# PowerInput.net
KiCad netlist of a schematic drawn in Altium Designer
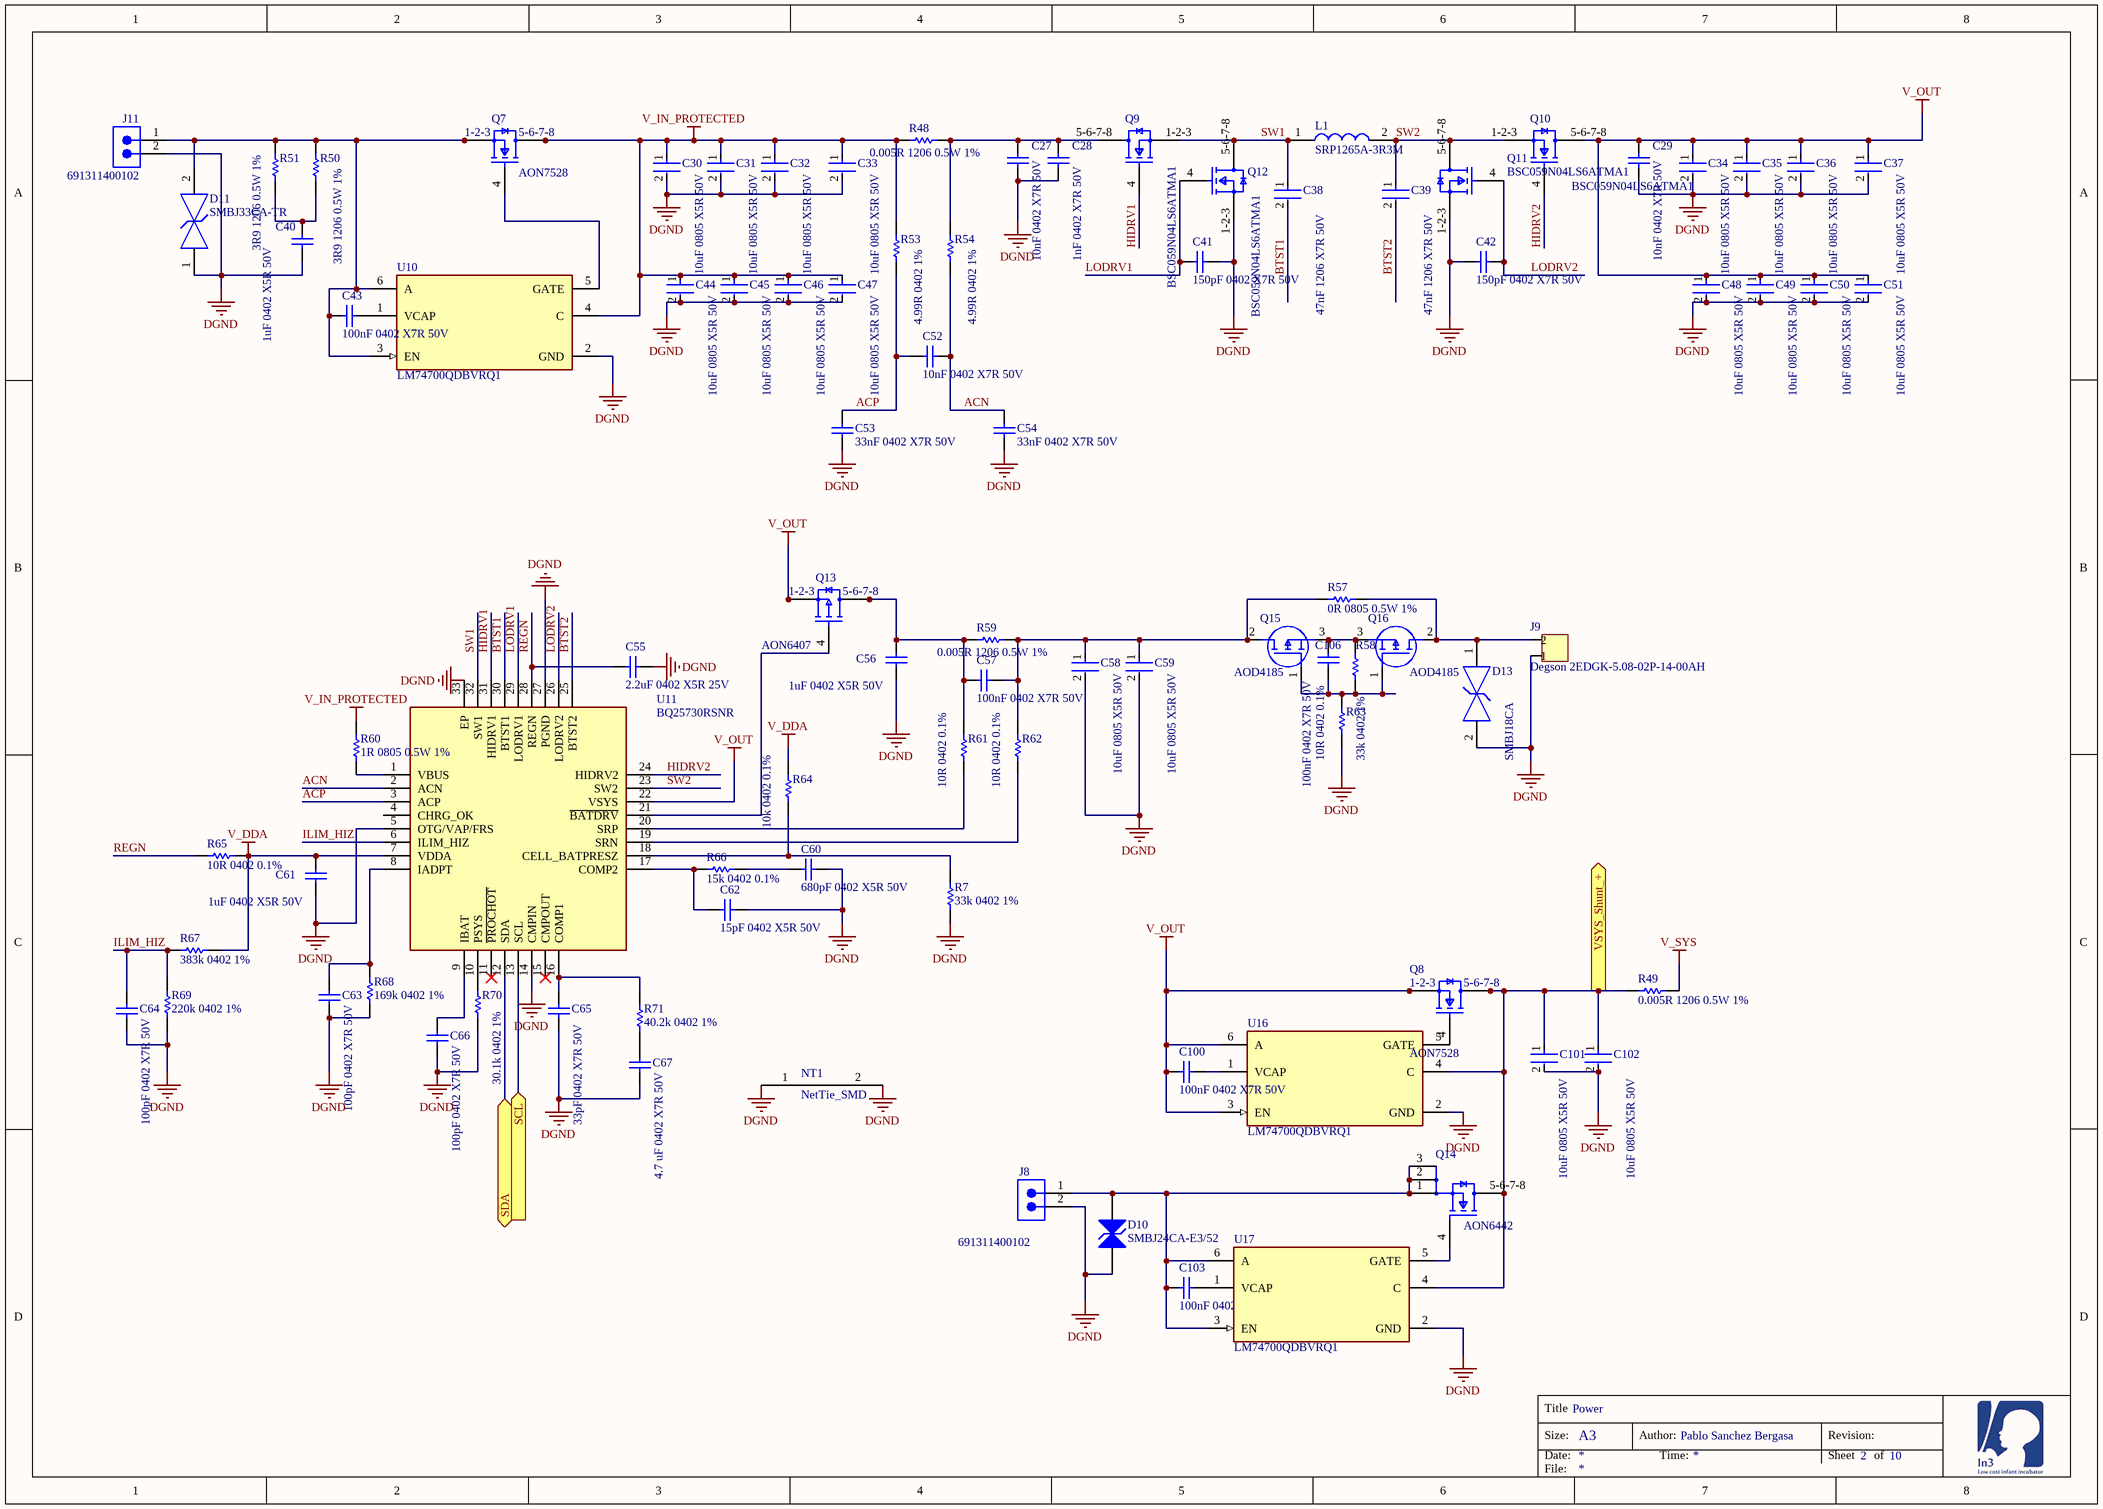
[diagram p0: PowerInput.SchDoc]

(export (version "E")
  (design (tool "Eeschema 10.0.6"))
  (components
    (comp (ref "C27")
      (value "10nF 0402 X7R 50V")
      (footprint "CAPC1005X55X25NL5T10")
      (libsource (lib "Altium Content Vault") (part "CAP-NP-2"))
    )
    (comp (ref "C28")
      (value "1nF 0402 X7R 50V")
      (footprint "CAPC1005X55X25NL5T10")
      (libsource (lib "Altium Content Vault") (part "CAP-NP-2"))
    )
    (comp (ref "C29")
      (value "10nF 0402 X7R 50V")
      (footprint "CAPC1005X55X25NL5T10")
      (libsource (lib "Altium Content Vault") (part "CAP-NP-2"))
    )
    (comp (ref "C30")
      (value "10uF 0805 X5R 50V")
      (footprint "FP-GRM21B-0_2-e0_2_0_7-MFG")
      (description "Chip Multilayer Ceramic Capacitors for General Purpose, 0805, 10uF, X5R, 15%, 10%, 35V")
      (fields (field (name "TOLERANCE") "10%"))
      (libsource (lib "Altium Content Vault") (part "b4654b650e69147ec39a6b967a45e02"))
    )
    (comp (ref "C31")
      (value "10uF 0805 X5R 50V")
      (footprint "FP-GRM21B-0_2-e0_2_0_7-MFG")
      (description "Chip Multilayer Ceramic Capacitors for General Purpose, 0805, 10uF, X5R, 15%, 10%, 35V")
      (fields (field (name "TOLERANCE") "10%"))
      (libsource (lib "Altium Content Vault") (part "b4654b650e69147ec39a6b967a45e02"))
    )
    (comp (ref "C32")
      (value "10uF 0805 X5R 50V")
      (footprint "FP-GRM21B-0_2-e0_2_0_7-MFG")
      (description "Chip Multilayer Ceramic Capacitors for General Purpose, 0805, 10uF, X5R, 15%, 10%, 35V")
      (fields (field (name "TOLERANCE") "10%"))
      (libsource (lib "Altium Content Vault") (part "b4654b650e69147ec39a6b967a45e02"))
    )
    (comp (ref "C33")
      (value "10uF 0805 X5R 50V")
      (footprint "FP-GRM21B-0_2-e0_2_0_7-MFG")
      (description "Chip Multilayer Ceramic Capacitors for General Purpose, 0805, 10uF, X5R, 15%, 10%, 35V")
      (fields (field (name "TOLERANCE") "10%"))
      (libsource (lib "Altium Content Vault") (part "b4654b650e69147ec39a6b967a45e02"))
    )
    (comp (ref "C34")
      (value "10uF 0805 X5R 50V")
      (footprint "FP-GRM21B-0_2-e0_2_0_7-MFG")
      (description "Chip Multilayer Ceramic Capacitors for General Purpose, 0805, 10uF, X5R, 15%, 10%, 35V")
      (fields (field (name "TOLERANCE") "10%"))
      (libsource (lib "Altium Content Vault") (part "b4654b650e69147ec39a6b967a45e02"))
    )
    (comp (ref "C35")
      (value "10uF 0805 X5R 50V")
      (footprint "FP-GRM21B-0_2-e0_2_0_7-MFG")
      (description "Chip Multilayer Ceramic Capacitors for General Purpose, 0805, 10uF, X5R, 15%, 10%, 35V")
      (fields (field (name "TOLERANCE") "10%"))
      (libsource (lib "Altium Content Vault") (part "b4654b650e69147ec39a6b967a45e02"))
    )
    (comp (ref "C36")
      (value "10uF 0805 X5R 50V")
      (footprint "FP-GRM21B-0_2-e0_2_0_7-MFG")
      (description "Chip Multilayer Ceramic Capacitors for General Purpose, 0805, 10uF, X5R, 15%, 10%, 35V")
      (fields (field (name "TOLERANCE") "10%"))
      (libsource (lib "Altium Content Vault") (part "b4654b650e69147ec39a6b967a45e02"))
    )
    (comp (ref "C37")
      (value "10uF 0805 X5R 50V")
      (footprint "FP-GRM21B-0_2-e0_2_0_7-MFG")
      (description "Chip Multilayer Ceramic Capacitors for General Purpose, 0805, 10uF, X5R, 15%, 10%, 35V")
      (fields (field (name "TOLERANCE") "10%"))
      (libsource (lib "Altium Content Vault") (part "b4654b650e69147ec39a6b967a45e02"))
    )
    (comp (ref "C38")
      (value "47nF 1206 X7R 50V")
      (footprint "FP-CC1206-FD-MFG")
      (description "CAP CER 10UF 50V X5R 1206")
      (fields (field (name "TOLERANCE") "10%"))
      (libsource (lib "Altium Content Vault") (part "b4654b650e69147ec39a6b967a45e02"))
    )
    (comp (ref "C39")
      (value "47nF 1206 X7R 50V")
      (footprint "FP-CC1206-FD-MFG")
      (description "CAP CER 10UF 50V X5R 1206")
      (fields (field (name "TOLERANCE") "10%"))
      (libsource (lib "Altium Content Vault") (part "b4654b650e69147ec39a6b967a45e02"))
    )
    (comp (ref "C40")
      (value "1uF 0402 X5R 50V")
      (footprint "CAPC1005X55X25NL5T10")
      (libsource (lib "Altium Content Vault") (part "CAP-NP-2"))
    )
    (comp (ref "C41")
      (value "150pF 0402 X7R 50V")
      (footprint "CAPC1005X55X25NL5T10")
      (libsource (lib "Altium Content Vault") (part "CAP-NP-2"))
    )
    (comp (ref "C42")
      (value "150pF 0402 X7R 50V")
      (footprint "CAPC1005X55X25NL5T10")
      (libsource (lib "Altium Content Vault") (part "CAP-NP-2"))
    )
    (comp (ref "C43")
      (value "100nF 0402 X7R 50V")
      (footprint "CAPC1005X55X25NL5T10")
      (libsource (lib "Altium Content Vault") (part "CAP-NP-2"))
    )
    (comp (ref "C44")
      (value "10uF 0805 X5R 50V")
      (footprint "FP-GRM21B-0_2-e0_2_0_7-MFG")
      (description "Chip Multilayer Ceramic Capacitors for General Purpose, 0805, 10uF, X5R, 15%, 10%, 35V")
      (fields (field (name "TOLERANCE") "10%"))
      (libsource (lib "Altium Content Vault") (part "b4654b650e69147ec39a6b967a45e02"))
    )
    (comp (ref "C45")
      (value "10uF 0805 X5R 50V")
      (footprint "FP-GRM21B-0_2-e0_2_0_7-MFG")
      (description "Chip Multilayer Ceramic Capacitors for General Purpose, 0805, 10uF, X5R, 15%, 10%, 35V")
      (fields (field (name "TOLERANCE") "10%"))
      (libsource (lib "Altium Content Vault") (part "b4654b650e69147ec39a6b967a45e02"))
    )
    (comp (ref "C46")
      (value "10uF 0805 X5R 50V")
      (footprint "FP-GRM21B-0_2-e0_2_0_7-MFG")
      (description "Chip Multilayer Ceramic Capacitors for General Purpose, 0805, 10uF, X5R, 15%, 10%, 35V")
      (fields (field (name "TOLERANCE") "10%"))
      (libsource (lib "Altium Content Vault") (part "b4654b650e69147ec39a6b967a45e02"))
    )
    (comp (ref "C47")
      (value "10uF 0805 X5R 50V")
      (footprint "FP-GRM21B-0_2-e0_2_0_7-MFG")
      (description "Chip Multilayer Ceramic Capacitors for General Purpose, 0805, 10uF, X5R, 15%, 10%, 35V")
      (fields (field (name "TOLERANCE") "10%"))
      (libsource (lib "Altium Content Vault") (part "b4654b650e69147ec39a6b967a45e02"))
    )
    (comp (ref "C48")
      (value "10uF 0805 X5R 50V")
      (footprint "FP-GRM21B-0_2-e0_2_0_7-MFG")
      (description "Chip Multilayer Ceramic Capacitors for General Purpose, 0805, 10uF, X5R, 15%, 10%, 35V")
      (fields (field (name "TOLERANCE") "10%"))
      (libsource (lib "Altium Content Vault") (part "b4654b650e69147ec39a6b967a45e02"))
    )
    (comp (ref "C49")
      (value "10uF 0805 X5R 50V")
      (footprint "FP-GRM21B-0_2-e0_2_0_7-MFG")
      (description "Chip Multilayer Ceramic Capacitors for General Purpose, 0805, 10uF, X5R, 15%, 10%, 35V")
      (fields (field (name "TOLERANCE") "10%"))
      (libsource (lib "Altium Content Vault") (part "b4654b650e69147ec39a6b967a45e02"))
    )
    (comp (ref "C50")
      (value "10uF 0805 X5R 50V")
      (footprint "FP-GRM21B-0_2-e0_2_0_7-MFG")
      (description "Chip Multilayer Ceramic Capacitors for General Purpose, 0805, 10uF, X5R, 15%, 10%, 35V")
      (fields (field (name "TOLERANCE") "10%"))
      (libsource (lib "Altium Content Vault") (part "b4654b650e69147ec39a6b967a45e02"))
    )
    (comp (ref "C51")
      (value "10uF 0805 X5R 50V")
      (footprint "FP-GRM21B-0_2-e0_2_0_7-MFG")
      (description "Chip Multilayer Ceramic Capacitors for General Purpose, 0805, 10uF, X5R, 15%, 10%, 35V")
      (fields (field (name "TOLERANCE") "10%"))
      (libsource (lib "Altium Content Vault") (part "b4654b650e69147ec39a6b967a45e02"))
    )
    (comp (ref "C52")
      (value "10nF 0402 X7R 50V")
      (footprint "CAPC1005X55X25NL5T10")
      (libsource (lib "Altium Content Vault") (part "CAP-NP-2"))
    )
    (comp (ref "C53")
      (value "33nF 0402 X7R 50V")
      (footprint "CAPC1005X55X25NL5T10")
      (libsource (lib "Altium Content Vault") (part "CAP-NP-2"))
    )
    (comp (ref "C54")
      (value "33nF 0402 X7R 50V")
      (footprint "CAPC1005X55X25NL5T10")
      (libsource (lib "Altium Content Vault") (part "CAP-NP-2"))
    )
    (comp (ref "C55")
      (value "2.2uF 0402 X5R 25V")
      (footprint "CAPC1005X55X25NL5T10")
      (libsource (lib "Altium Content Vault") (part "CAP-NP-2"))
    )
    (comp (ref "C56")
      (value "1uF 0402 X5R 50V")
      (footprint "CAPC1005X55X25NL5T10")
      (libsource (lib "Altium Content Vault") (part "CAP-NP-2"))
    )
    (comp (ref "C57")
      (value "100nF 0402 X7R 50V")
      (footprint "CAPC1005X55X25NL5T10")
      (libsource (lib "Altium Content Vault") (part "CAP-NP-2"))
    )
    (comp (ref "C58")
      (value "10uF 0805 X5R 50V")
      (footprint "FP-GRM21B-0_2-e0_2_0_7-MFG")
      (description "Chip Multilayer Ceramic Capacitors for General Purpose, 0805, 10uF, X5R, 15%, 10%, 35V")
      (fields (field (name "TOLERANCE") "10%"))
      (libsource (lib "Altium Content Vault") (part "b4654b650e69147ec39a6b967a45e02"))
    )
    (comp (ref "C59")
      (value "10uF 0805 X5R 50V")
      (footprint "FP-GRM21B-0_2-e0_2_0_7-MFG")
      (description "Chip Multilayer Ceramic Capacitors for General Purpose, 0805, 10uF, X5R, 15%, 10%, 35V")
      (fields (field (name "TOLERANCE") "10%"))
      (libsource (lib "Altium Content Vault") (part "b4654b650e69147ec39a6b967a45e02"))
    )
    (comp (ref "C60")
      (value "680pF 0402 X5R 50V")
      (footprint "CAPC1005X55X25NL5T10")
      (libsource (lib "Altium Content Vault") (part "CAP-NP-2"))
    )
    (comp (ref "C61")
      (value "1uF 0402 X5R 50V")
      (footprint "CAPC1005X55X25NL5T10")
      (libsource (lib "Altium Content Vault") (part "CAP-NP-2"))
    )
    (comp (ref "C62")
      (value "15pF 0402 X5R 50V")
      (footprint "CAPC1005X55X25NL5T10")
      (libsource (lib "Altium Content Vault") (part "CAP-NP-2"))
    )
    (comp (ref "C63")
      (value "100pF 0402 X7R 50V")
      (footprint "CAPC1005X55X25NL5T10")
      (libsource (lib "Altium Content Vault") (part "CAP-NP-2"))
    )
    (comp (ref "C64")
      (value "100pF 0402 X7R 50V")
      (footprint "CAPC1005X55X25NL5T10")
      (libsource (lib "Altium Content Vault") (part "CAP-NP-2"))
    )
    (comp (ref "C65")
      (value "33pF 0402 X7R 50V")
      (footprint "CAPC1005X55X25NL5T10")
      (libsource (lib "Altium Content Vault") (part "CAP-NP-2"))
    )
    (comp (ref "C66")
      (value "100pF 0402 X7R 50V")
      (footprint "CAPC1005X55X25NL5T10")
      (libsource (lib "Altium Content Vault") (part "CAP-NP-2"))
    )
    (comp (ref "C67")
      (value "4.7 uF 0402 X7R 50V")
      (footprint "CAPC1005X55X25NL5T10")
      (libsource (lib "Altium Content Vault") (part "CAP-NP-2"))
    )
    (comp (ref "C100")
      (value "100nF 0402 X7R 50V")
      (footprint "CAPC1005X55X25NL5T10")
      (libsource (lib "Altium Content Vault") (part "CAP-NP-2"))
    )
    (comp (ref "C101")
      (value "10uF 0805 X5R 50V")
      (footprint "FP-GRM21B-0_2-e0_2_0_7-MFG")
      (description "Chip Multilayer Ceramic Capacitors for General Purpose, 0805, 10uF, X5R, 15%, 10%, 35V")
      (fields (field (name "TOLERANCE") "10%"))
      (libsource (lib "Altium Content Vault") (part "b4654b650e69147ec39a6b967a45e02"))
    )
    (comp (ref "C102")
      (value "10uF 0805 X5R 50V")
      (footprint "FP-GRM21B-0_2-e0_2_0_7-MFG")
      (description "Chip Multilayer Ceramic Capacitors for General Purpose, 0805, 10uF, X5R, 15%, 10%, 35V")
      (fields (field (name "TOLERANCE") "10%"))
      (libsource (lib "Altium Content Vault") (part "b4654b650e69147ec39a6b967a45e02"))
    )
    (comp (ref "C103")
      (value "100nF 0402 X7R 50V")
      (footprint "CAPC1005X55X25NL5T10")
      (libsource (lib "Altium Content Vault") (part "CAP-NP-2"))
    )
    (comp (ref "C106")
      (value "100nF 0402 X7R 50V")
      (footprint "CAPC1005X55X25NL5T10")
      (libsource (lib "Altium Content Vault") (part "CAP-NP-2"))
    )
    (comp (ref "D10")
      (value "SMBJ24CA-E3/52")
      (footprint "VISH-DO-214AA-A-2_V")
      (fields (field (name "MANUFACTURER") "Vishay"))
      (libsource (lib "Altium Content Vault") (part "DZEN-AA-2"))
    )
    (comp (ref "D11")
      (value "SMBJ33CA-TR")
      (footprint "FP-SMB-CA-MFG")
      (description "TVS DIODE 33V 69.7V SMB")
      (fields
        (field (name "OCTOPART") "https://octopart.com/smbj33ca-tr-stmicroelectronics-347069")
        (field (name "MANUFACTURER") "STMicroelectronics")
      )
      (libsource (lib "Altium Content Vault") (part "11bd9d59d340f0612179daf16ad9b72"))
    )
    (comp (ref "D13")
      (value "SMBJ18CA")
      (footprint "FP-SMBJ-MFG")
      (description "TVS DIODE 18V 29.2V DO214AA")
      (fields
        (field (name "MANUFACTURER") "Littelfuse Inc")
        (field (name "OCTOPART") "https://octopart.com/smbj18ca-littelfuse-350695")
      )
      (libsource (lib "Altium Content Vault") (part "876f4347bf90aa6f500f43e3cd03972"))
    )
    (comp (ref "J8")
      (value "691311400102")
      (footprint "691311400102")
      (description "7.62MM Pitch Straight Pluggable Term Block, Pcb Header, Through Hole, 2 Way")
      (fields (field (name "VOLTAGE") "300V"))
      (libsource (lib "Altium Content Vault") (part "TBL - 1R - 02P - Male"))
    )
    (comp (ref "J9")
      (value "Degson 2EDGK-5.08-02P-14-00AH")
      (footprint "PCB-h4cyb3wxd4gf7j132tzl-1")
      (description "Terminal block, 5mm 2 Pos, through hole male.")
      (fields (field (name "MANUFACTURER PART NUMBER") "2EDGK-5.08-02P-14-00AH + 2EDGVC-5.08-02P"))
      (libsource (lib "in3ator") (part "CMP-7a42b7ee166ba585-1"))
    )
    (comp (ref "J11")
      (value "691311400102")
      (footprint "691311400102")
      (description "7.62MM Pitch Straight Pluggable Term Block, Pcb Header, Through Hole, 2 Way")
      (fields (field (name "VOLTAGE") "300V"))
      (libsource (lib "Altium Content Vault") (part "TBL - 1R - 02P - Male"))
    )
    (comp (ref "L1")
      (value "SRP1265A-3R3M")
      (footprint "SamacSys:INDPM135125X650N")
      (description "Inductor")
      (fields (field (name "MOUSER PART NUMBER") "652-SRP1265A-3R3M"))
      (libsource (lib "*") (part "SRP1265A-3R3M"))
    )
    (comp (ref "NT1")
      (value "NetTie_SMD")
      (footprint "NETTIE_SMD")
      (description "Net Tie SMD")
      (libsource (lib "net_tie") (part "NetTie_SMD"))
    )
    (comp (ref "Q7")
      (value "AON7528")
      (footprint "SamacSys:AON7520")
      (description "MOSFET (N-Channel)")
      (libsource (lib "SamacSys") (part "AON7528"))
    )
    (comp (ref "Q8")
      (value "AON7528")
      (footprint "SamacSys:AON7520")
      (description "MOSFET (N-Channel)")
      (libsource (lib "SamacSys") (part "AON7528"))
    )
    (comp (ref "Q9")
      (value "BSC059N04LS6ATMA1")
      (footprint "FP-PG-TDSON-8-MFG")
      (description "TRENCH <= 40V")
      (fields
        (field (name "MANUFACTURER") "Infineon")
        (field (name "OCTOPART") "https://octopart.com/bsc059n04ls6atma1-infineon-98039929")
      )
      (libsource (lib "Altium Content Vault") (part "1b0cff3a23bd3632373e77d40b07099"))
    )
    (comp (ref "Q10")
      (value "BSC059N04LS6ATMA1")
      (footprint "FP-PG-TDSON-8-MFG")
      (description "TRENCH <= 40V")
      (fields
        (field (name "MANUFACTURER") "Infineon")
        (field (name "OCTOPART") "https://octopart.com/bsc059n04ls6atma1-infineon-98039929")
      )
      (libsource (lib "Altium Content Vault") (part "1b0cff3a23bd3632373e77d40b07099"))
    )
    (comp (ref "Q11")
      (value "BSC059N04LS6ATMA1")
      (footprint "FP-PG-TDSON-8-MFG")
      (description "TRENCH <= 40V")
      (fields
        (field (name "MANUFACTURER") "Infineon")
        (field (name "OCTOPART") "https://octopart.com/bsc059n04ls6atma1-infineon-98039929")
      )
      (libsource (lib "Altium Content Vault") (part "1b0cff3a23bd3632373e77d40b07099"))
    )
    (comp (ref "Q12")
      (value "BSC059N04LS6ATMA1")
      (footprint "FP-PG-TDSON-8-MFG")
      (description "TRENCH <= 40V")
      (fields
        (field (name "MANUFACTURER") "Infineon")
        (field (name "OCTOPART") "https://octopart.com/bsc059n04ls6atma1-infineon-98039929")
      )
      (libsource (lib "Altium Content Vault") (part "1b0cff3a23bd3632373e77d40b07099"))
    )
    (comp (ref "Q13")
      (value "AON6407")
      (footprint "SamacSys:AON6414A")
      (description "MOSFET (P-Channel)")
      (libsource (lib "SamacSys") (part "AON6407"))
    )
    (comp (ref "Q14")
      (value "AON6442")
      (footprint "FP-DFN5x6_8L_EP1_P-MFG")
      (description "MOSFET N-CH 40V 22A/32A 8DFN")
      (libsource (lib "Altium Content Vault") (part "7382af88e928fdc71488234cfaaf11c"))
    )
    (comp (ref "Q15")
      (value "AOD4185")
      (footprint "SamacSys:AOD4185")
      (description "MOSFET (P-Channel)")
      (libsource (lib "*") (part "AOD4185"))
    )
    (comp (ref "Q16")
      (value "AOD4185")
      (footprint "SamacSys:AOD4185")
      (description "MOSFET (P-Channel)")
      (libsource (lib "*") (part "AOD4185"))
    )
    (comp (ref "R7")
      (value "33k 0402 1%")
      (footprint "RESC1005X40X25ML05T10")
      (libsource (lib "Altium Content Vault") (part "RES"))
    )
    (comp (ref "R48")
      (value "0.005R 1206 0.5W 1%")
      (footprint "CAPC3216X180X55ML20T25")
      (fields (field (name "MANUFACTURER PART NUMBER") "WSLP12065L000FEA") (field (name "POWER") "1W"))
      (libsource (lib "in3ator") (part "CMP-0abdc173b10ad57a-1"))
    )
    (comp (ref "R49")
      (value "0.005R 1206 0.5W 1%")
      (footprint "CAPC3216X180X55ML20T25")
      (fields (field (name "MANUFACTURER PART NUMBER") "WSLP12065L000FEA") (field (name "POWER") "1W"))
      (libsource (lib "in3ator") (part "CMP-0abdc173b10ad57a-1"))
    )
    (comp (ref "R50")
      (value "3R9 1206 0.5W 1%")
      (footprint "CAPC3216X180X55ML20T25")
      (fields (field (name "MANUFACTURER PART NUMBER") "WSLP12065L000FEA") (field (name "POWER") "1W"))
      (libsource (lib "in3ator") (part "CMP-0abdc173b10ad57a-1"))
    )
    (comp (ref "R51")
      (value "3R9 1206 0.5W 1%")
      (footprint "CAPC3216X180X55ML20T25")
      (fields (field (name "MANUFACTURER PART NUMBER") "WSLP12065L000FEA") (field (name "POWER") "1W"))
      (libsource (lib "in3ator") (part "CMP-0abdc173b10ad57a-1"))
    )
    (comp (ref "R53")
      (value "4.99R 0402 1%")
      (footprint "RESC1005X40X25ML05T10")
      (libsource (lib "Altium Content Vault") (part "RES"))
    )
    (comp (ref "R54")
      (value "4.99R 0402 1%")
      (footprint "RESC1005X40X25ML05T10")
      (libsource (lib "Altium Content Vault") (part "RES"))
    )
    (comp (ref "R57")
      (value "0R 0805 0.5W 1%")
      (footprint "RESC2013X65X40LL15T20")
      (description "Chip Resistor, 0 Ohm, 0.125 W, -55 to 125 degC, 0805 (2012 Metric), RoHS, Tape and Reel")
      (fields (field (name "TOLERANCE") "0%") (field (name "MANUFACTURER") "TE Connectivity"))
      (libsource (lib "Altium Content Vault") (part "RES-2"))
    )
    (comp (ref "R58")
      (value "33k 0402 1%")
      (footprint "RESC1005X40X25ML05T10")
      (libsource (lib "Altium Content Vault") (part "RES"))
    )
    (comp (ref "R59")
      (value "0.005R 1206 0.5W 1%")
      (footprint "CAPC3216X180X55ML20T25")
      (fields (field (name "MANUFACTURER PART NUMBER") "WSLP12065L000FEA") (field (name "POWER") "1W"))
      (libsource (lib "in3ator") (part "CMP-0abdc173b10ad57a-1"))
    )
    (comp (ref "R60")
      (value "1R 0805 0.5W 1%")
      (footprint "RESC2013X65X40LL15T20")
      (description "Chip Resistor, 0 Ohm, 0.125 W, -55 to 125 degC, 0805 (2012 Metric), RoHS, Tape and Reel")
      (fields (field (name "TOLERANCE") "0%") (field (name "MANUFACTURER") "TE Connectivity"))
      (libsource (lib "Altium Content Vault") (part "RES-2"))
    )
    (comp (ref "R61")
      (value "10R 0402 0.1%")
      (footprint "RESC1005X40X25ML05T10")
      (libsource (lib "Altium Content Vault") (part "RES"))
    )
    (comp (ref "R62")
      (value "10R 0402 0.1%")
      (footprint "RESC1005X40X25ML05T10")
      (libsource (lib "Altium Content Vault") (part "RES"))
    )
    (comp (ref "R63")
      (value "10R 0402 0.1%")
      (footprint "RESC1005X40X25ML05T10")
      (libsource (lib "Altium Content Vault") (part "RES"))
    )
    (comp (ref "R64")
      (value "10k 0402 0.1%")
      (footprint "RESC1005X40X25ML05T10")
      (libsource (lib "Altium Content Vault") (part "RES"))
    )
    (comp (ref "R65")
      (value "10R 0402 0.1%")
      (footprint "RESC1005X40X25ML05T10")
      (libsource (lib "Altium Content Vault") (part "RES"))
    )
    (comp (ref "R66")
      (value "15k 0402 0.1%")
      (footprint "RESC1005X40X25ML05T10")
      (libsource (lib "Altium Content Vault") (part "RES"))
    )
    (comp (ref "R67")
      (value "383k 0402 1%")
      (footprint "RESC1005X40X25ML05T10")
      (libsource (lib "Altium Content Vault") (part "RES"))
    )
    (comp (ref "R68")
      (value "169k 0402 1%")
      (footprint "RESC1005X40X25ML05T10")
      (libsource (lib "Altium Content Vault") (part "RES"))
    )
    (comp (ref "R69")
      (value "220k 0402 1%")
      (footprint "RESC1005X40X25ML05T10")
      (libsource (lib "Altium Content Vault") (part "RES"))
    )
    (comp (ref "R70")
      (value "30.1k 0402 1%")
      (footprint "RESC1005X40X25ML05T10")
      (libsource (lib "Altium Content Vault") (part "RES"))
    )
    (comp (ref "R71")
      (value "40.2k 0402 1%")
      (footprint "RESC1005X40X25ML05T10")
      (libsource (lib "Altium Content Vault") (part "RES"))
    )
    (comp (ref "U10")
      (value "LM74700QDBVRQ1")
      (footprint "FP-DBV0006A-MFG")
      (description "POWER MANAGEMENT")
      (fields
        (field (name "OCTOPART") "https://octopart.com/lm74700qdbvrq1-texas+instruments-87700446")
        (field (name "MANUFACTURER") "Texas Instruments")
      )
      (libsource (lib "Altium Content Vault") (part "6c1cf2fb71eda42a9abfc060c5aeec2"))
    )
    (comp (ref "U11")
      (value "BQ25730RSNR")
      (footprint "SamacSys:QFN40P400X400X80-33N-D")
      (description "Integrated Circuit")
      (fields (field (name "MOUSER PART NUMBER") "595-BQ25730RSNR"))
      (libsource (lib "*") (part "BQ25730RSNR"))
    )
    (comp (ref "U16")
      (value "LM74700QDBVRQ1")
      (footprint "FP-DBV0006A-MFG")
      (description "POWER MANAGEMENT")
      (fields
        (field (name "OCTOPART") "https://octopart.com/lm74700qdbvrq1-texas+instruments-87700446")
        (field (name "MANUFACTURER") "Texas Instruments")
      )
      (libsource (lib "Altium Content Vault") (part "6c1cf2fb71eda42a9abfc060c5aeec2"))
    )
    (comp (ref "U17")
      (value "LM74700QDBVRQ1")
      (footprint "FP-DBV0006A-MFG")
      (description "POWER MANAGEMENT")
      (fields
        (field (name "OCTOPART") "https://octopart.com/lm74700qdbvrq1-texas+instruments-87700446")
        (field (name "MANUFACTURER") "Texas Instruments")
      )
      (libsource (lib "Altium Content Vault") (part "6c1cf2fb71eda42a9abfc060c5aeec2"))
    )
  )
  (nets
    (net (code "1") (name "/ACN") (class "Default")
      (node (ref "C52") (pin "1") (pinfunction "1_1") (pintype "passive"))
      (node (ref "C54") (pin "1") (pinfunction "1_1") (pintype "passive"))
      (node (ref "R54") (pin "1") (pinfunction "1_1") (pintype "passive"))
      (node (ref "U11") (pin "2") (pinfunction "ACN_2") (pintype "passive"))
    )
    (net (code "2") (name "/ACP") (class "Default")
      (node (ref "C52") (pin "2") (pinfunction "2_2") (pintype "passive"))
      (node (ref "C53") (pin "1") (pinfunction "1_1") (pintype "passive"))
      (node (ref "R53") (pin "1") (pinfunction "1_1") (pintype "passive"))
      (node (ref "U11") (pin "3") (pinfunction "ACP_3") (pintype "passive"))
    )
    (net (code "3") (name "/BTST1") (class "Default")
      (node (ref "C38") (pin "2") (pinfunction "2_2") (pintype "passive"))
      (node (ref "U11") (pin "30") (pinfunction "BTST1_30") (pintype "passive"))
    )
    (net (code "4") (name "/BTST2") (class "Default")
      (node (ref "C39") (pin "2") (pinfunction "2_2") (pintype "passive"))
      (node (ref "U11") (pin "25") (pinfunction "BTST2_25") (pintype "passive"))
    )
    (net (code "5") (name "/HIDRV1") (class "Default")
      (node (ref "Q9") (pin "4") (pinfunction "G_4") (pintype "passive"))
      (node (ref "U11") (pin "31") (pinfunction "HIDRV1_31") (pintype "passive"))
    )
    (net (code "6") (name "/HIDRV2") (class "Default")
      (node (ref "Q10") (pin "4") (pinfunction "G_4") (pintype "passive"))
      (node (ref "U11") (pin "24") (pinfunction "HIDRV2_24") (pintype "passive"))
    )
    (net (code "7") (name "/ILIM_HIZ") (class "Default")
      (node (ref "C64") (pin "1") (pinfunction "1_1") (pintype "passive"))
      (node (ref "R67") (pin "2") (pinfunction "2_2") (pintype "passive"))
      (node (ref "R69") (pin "1") (pinfunction "1_1") (pintype "passive"))
      (node (ref "U11") (pin "6") (pinfunction "ILIM_HIZ_6") (pintype "passive"))
    )
    (net (code "8") (name "/LODRV1") (class "Default")
      (node (ref "C41") (pin "2") (pinfunction "2_2") (pintype "passive"))
      (node (ref "Q12") (pin "4") (pinfunction "G_4") (pintype "passive"))
      (node (ref "U11") (pin "29") (pinfunction "LODRV1_29") (pintype "passive"))
    )
    (net (code "9") (name "/LODRV2") (class "Default")
      (node (ref "C42") (pin "2") (pinfunction "2_2") (pintype "passive"))
      (node (ref "Q11") (pin "4") (pinfunction "G_4") (pintype "passive"))
      (node (ref "U11") (pin "26") (pinfunction "LODRV2_26") (pintype "passive"))
    )
    (net (code "10") (name "/REGN") (class "Default")
      (node (ref "C55") (pin "2") (pinfunction "2_2") (pintype "passive"))
      (node (ref "R65") (pin "2") (pinfunction "2_2") (pintype "passive"))
      (node (ref "U11") (pin "28") (pinfunction "REGN_28") (pintype "passive"))
    )
    (net (code "11") (name "/SCL") (class "Default")
      (node (ref "U11") (pin "13") (pinfunction "SCL_13") (pintype "passive"))
    )
    (net (code "12") (name "/SDA") (class "Default")
      (node (ref "U11") (pin "12") (pinfunction "SDA_12") (pintype "passive"))
    )
    (net (code "13") (name "/SW1") (class "Default")
      (node (ref "C38") (pin "1") (pinfunction "1_1") (pintype "passive"))
      (node (ref "L1") (pin "1") (pinfunction "1_1") (pintype "passive"))
      (node (ref "Q12") (pin "5-6-7-8") (pinfunction "D_5-6-7-8") (pintype "passive"))
      (node (ref "Q9") (pin "1-2-3") (pinfunction "S_1-2-3") (pintype "passive"))
      (node (ref "U11") (pin "32") (pinfunction "SW1_32") (pintype "passive"))
    )
    (net (code "14") (name "/SW2") (class "Default")
      (node (ref "C39") (pin "1") (pinfunction "1_1") (pintype "passive"))
      (node (ref "L1") (pin "2") (pinfunction "2_2") (pintype "passive"))
      (node (ref "Q10") (pin "1-2-3") (pinfunction "S_1-2-3") (pintype "passive"))
      (node (ref "Q11") (pin "5-6-7-8") (pinfunction "D_5-6-7-8") (pintype "passive"))
      (node (ref "U11") (pin "23") (pinfunction "SW2_23") (pintype "passive"))
    )
    (net (code "15") (name "/VSYS_Shunt_+") (class "Default")
      (node (ref "C101") (pin "1") (pinfunction "1_1") (pintype "passive"))
      (node (ref "C102") (pin "1") (pinfunction "1_1") (pintype "passive"))
      (node (ref "Q14") (pin "5-6-7-8") (pinfunction "D_5-6-7-8") (pintype "passive"))
      (node (ref "Q8") (pin "5") (pinfunction "D_5") (pintype "passive"))
      (node (ref "Q8") (pin "6") (pinfunction "D_6") (pintype "passive"))
      (node (ref "Q8") (pin "7") (pinfunction "D_7") (pintype "passive"))
      (node (ref "Q8") (pin "8") (pinfunction "D_8") (pintype "passive"))
      (node (ref "Q8") (pin "9") (pinfunction "D_9") (pintype "passive"))
      (node (ref "R49") (pin "2") (pinfunction "2_2") (pintype "passive"))
      (node (ref "U16") (pin "4") (pinfunction "C_4") (pintype "passive"))
      (node (ref "U17") (pin "4") (pinfunction "C_4") (pintype "passive"))
    )
    (net (code "16") (name "DGND") (class "Default")
      (node (ref "C101") (pin "2") (pinfunction "2_2") (pintype "passive"))
      (node (ref "C102") (pin "2") (pinfunction "2_2") (pintype "passive"))
      (node (ref "C27") (pin "1") (pinfunction "1_1") (pintype "passive"))
      (node (ref "C28") (pin "1") (pinfunction "1_1") (pintype "passive"))
      (node (ref "C29") (pin "1") (pinfunction "1_1") (pintype "passive"))
      (node (ref "C30") (pin "2") (pinfunction "2_2") (pintype "passive"))
      (node (ref "C31") (pin "2") (pinfunction "2_2") (pintype "passive"))
      (node (ref "C32") (pin "2") (pinfunction "2_2") (pintype "passive"))
      (node (ref "C33") (pin "2") (pinfunction "2_2") (pintype "passive"))
      (node (ref "C34") (pin "2") (pinfunction "2_2") (pintype "passive"))
      (node (ref "C35") (pin "2") (pinfunction "2_2") (pintype "passive"))
      (node (ref "C36") (pin "2") (pinfunction "2_2") (pintype "passive"))
      (node (ref "C37") (pin "2") (pinfunction "2_2") (pintype "passive"))
      (node (ref "C40") (pin "1") (pinfunction "1_1") (pintype "passive"))
      (node (ref "C41") (pin "1") (pinfunction "1_1") (pintype "passive"))
      (node (ref "C42") (pin "1") (pinfunction "1_1") (pintype "passive"))
      (node (ref "C44") (pin "2") (pinfunction "2_2") (pintype "passive"))
      (node (ref "C45") (pin "2") (pinfunction "2_2") (pintype "passive"))
      (node (ref "C46") (pin "2") (pinfunction "2_2") (pintype "passive"))
      (node (ref "C47") (pin "2") (pinfunction "2_2") (pintype "passive"))
      (node (ref "C48") (pin "2") (pinfunction "2_2") (pintype "passive"))
      (node (ref "C49") (pin "2") (pinfunction "2_2") (pintype "passive"))
      (node (ref "C50") (pin "2") (pinfunction "2_2") (pintype "passive"))
      (node (ref "C51") (pin "2") (pinfunction "2_2") (pintype "passive"))
      (node (ref "C53") (pin "2") (pinfunction "2_2") (pintype "passive"))
      (node (ref "C54") (pin "2") (pinfunction "2_2") (pintype "passive"))
      (node (ref "C55") (pin "1") (pinfunction "1_1") (pintype "passive"))
      (node (ref "C56") (pin "1") (pinfunction "1_1") (pintype "passive"))
      (node (ref "C58") (pin "2") (pinfunction "2_2") (pintype "passive"))
      (node (ref "C59") (pin "2") (pinfunction "2_2") (pintype "passive"))
      (node (ref "C60") (pin "1") (pinfunction "1_1") (pintype "passive"))
      (node (ref "C61") (pin "1") (pinfunction "1_1") (pintype "passive"))
      (node (ref "C62") (pin "1") (pinfunction "1_1") (pintype "passive"))
      (node (ref "C63") (pin "2") (pinfunction "2_2") (pintype "passive"))
      (node (ref "C64") (pin "2") (pinfunction "2_2") (pintype "passive"))
      (node (ref "C65") (pin "2") (pinfunction "2_2") (pintype "passive"))
      (node (ref "C66") (pin "2") (pinfunction "2_2") (pintype "passive"))
      (node (ref "C67") (pin "2") (pinfunction "2_2") (pintype "passive"))
      (node (ref "D10") (pin "1") (pinfunction "A_1") (pintype "passive"))
      (node (ref "D11") (pin "1") (pinfunction "1_1") (pintype "passive"))
      (node (ref "D13") (pin "2") (pinfunction "2_2") (pintype "passive"))
      (node (ref "J11") (pin "2") (pinfunction "2_2") (pintype "passive"))
      (node (ref "J8") (pin "2") (pinfunction "2_2") (pintype "passive"))
      (node (ref "J9") (pin "1") (pinfunction "1_1") (pintype "passive"))
      (node (ref "NT1") (pin "1") (pinfunction "1_1") (pintype "passive"))
      (node (ref "NT1") (pin "2") (pinfunction "2_2") (pintype "passive"))
      (node (ref "Q11") (pin "1-2-3") (pinfunction "S_1-2-3") (pintype "passive"))
      (node (ref "Q12") (pin "1-2-3") (pinfunction "S_1-2-3") (pintype "passive"))
      (node (ref "R63") (pin "1") (pinfunction "1_1") (pintype "passive"))
      (node (ref "R68") (pin "2") (pinfunction "2_2") (pintype "passive"))
      (node (ref "R69") (pin "2") (pinfunction "2_2") (pintype "passive"))
      (node (ref "R7") (pin "2") (pinfunction "2_2") (pintype "passive"))
      (node (ref "R70") (pin "2") (pinfunction "2_2") (pintype "passive"))
      (node (ref "U10") (pin "2") (pinfunction "GND_2") (pintype "power_in"))
      (node (ref "U11") (pin "14") (pinfunction "CMPIN_14") (pintype "passive"))
      (node (ref "U11") (pin "27") (pinfunction "PGND_27") (pintype "passive"))
      (node (ref "U11") (pin "33") (pinfunction "EP_33") (pintype "passive"))
      (node (ref "U11") (pin "5") (pinfunction "OTG/VAP/FRS_5") (pintype "passive"))
      (node (ref "U16") (pin "2") (pinfunction "GND_2") (pintype "power_in"))
      (node (ref "U17") (pin "2") (pinfunction "GND_2") (pintype "power_in"))
    )
    (net (code "17") (name "Net-(C40-Pad2)") (class "Default")
      (node (ref "C40") (pin "2") (pinfunction "2_2") (pintype "passive"))
      (node (ref "R50") (pin "2") (pinfunction "2_2") (pintype "passive"))
      (node (ref "R51") (pin "2") (pinfunction "2_2") (pintype "passive"))
    )
    (net (code "18") (name "Net-(C56-Pad2)") (class "Default")
      (node (ref "C56") (pin "2") (pinfunction "2_2") (pintype "passive"))
      (node (ref "C57") (pin "2") (pinfunction "2_2") (pintype "passive"))
      (node (ref "Q13") (pin "5") (pinfunction "D_5") (pintype "passive"))
      (node (ref "Q13") (pin "6") (pinfunction "D_6") (pintype "passive"))
      (node (ref "Q13") (pin "7") (pinfunction "D_7") (pintype "passive"))
      (node (ref "Q13") (pin "8") (pinfunction "D_8") (pintype "passive"))
      (node (ref "Q13") (pin "9") (pinfunction "D_9") (pintype "passive"))
      (node (ref "R59") (pin "2") (pinfunction "2_2") (pintype "passive"))
      (node (ref "R61") (pin "2") (pinfunction "2_2") (pintype "passive"))
    )
    (net (code "19") (name "Net-(C60-Pad2)") (class "Default")
      (node (ref "C60") (pin "2") (pinfunction "2_2") (pintype "passive"))
      (node (ref "R66") (pin "1") (pinfunction "1_1") (pintype "passive"))
    )
    (net (code "20") (name "Net-(C67-Pad1)") (class "Default")
      (node (ref "C67") (pin "1") (pinfunction "1_1") (pintype "passive"))
      (node (ref "R71") (pin "2") (pinfunction "2_2") (pintype "passive"))
    )
    (net (code "21") (name "Net-(Q7-1-2-3)") (class "Default")
      (node (ref "C43") (pin "2") (pinfunction "2_2") (pintype "passive"))
      (node (ref "D11") (pin "2") (pinfunction "2_2") (pintype "passive"))
      (node (ref "J11") (pin "1") (pinfunction "1_1") (pintype "passive"))
      (node (ref "Q7") (pin "1") (pinfunction "1-2-3_1") (pintype "passive"))
      (node (ref "Q7") (pin "2") (pinfunction "S_2") (pintype "passive"))
      (node (ref "Q7") (pin "3") (pinfunction "S_3") (pintype "passive"))
      (node (ref "R50") (pin "1") (pinfunction "1_1") (pintype "passive"))
      (node (ref "R51") (pin "1") (pinfunction "1_1") (pintype "passive"))
      (node (ref "U10") (pin "3") (pinfunction "EN_3") (pintype "input"))
      (node (ref "U10") (pin "6") (pinfunction "A_6") (pintype "passive"))
    )
    (net (code "22") (name "Net-(Q7-G)") (class "Default")
      (node (ref "Q7") (pin "4") (pinfunction "G_4") (pintype "passive"))
      (node (ref "U10") (pin "5") (pinfunction "GATE_5") (pintype "passive"))
    )
    (net (code "23") (name "Net-(Q8-G)") (class "Default")
      (node (ref "Q8") (pin "4") (pinfunction "G_4") (pintype "passive"))
      (node (ref "U16") (pin "5") (pinfunction "GATE_5") (pintype "passive"))
    )
    (net (code "24") (name "Net-(Q9-D)") (class "Default")
      (node (ref "C27") (pin "2") (pinfunction "2_2") (pintype "passive"))
      (node (ref "C28") (pin "2") (pinfunction "2_2") (pintype "passive"))
      (node (ref "Q9") (pin "5-6-7-8") (pinfunction "D_5-6-7-8") (pintype "passive"))
      (node (ref "R48") (pin "1") (pinfunction "1_1") (pintype "passive"))
      (node (ref "R54") (pin "2") (pinfunction "2_2") (pintype "passive"))
    )
    (net (code "25") (name "Net-(Q13-G)") (class "Default")
      (node (ref "Q13") (pin "4") (pinfunction "G_4") (pintype "passive"))
      (node (ref "U11") (pin "21") (pinfunction "~{BATDRV}_21") (pintype "passive"))
    )
    (net (code "26") (name "Net-(Q14-G)") (class "Default")
      (node (ref "Q14") (pin "4") (pinfunction "G_4") (pintype "passive"))
      (node (ref "U17") (pin "5") (pinfunction "GATE_5") (pintype "passive"))
    )
    (net (code "27") (name "Net-(Q15-D)") (class "Default")
      (node (ref "C57") (pin "1") (pinfunction "1_1") (pintype "passive"))
      (node (ref "C58") (pin "1") (pinfunction "1_1") (pintype "passive"))
      (node (ref "C59") (pin "1") (pinfunction "1_1") (pintype "passive"))
      (node (ref "Q15") (pin "2") (pinfunction "D_2") (pintype "passive"))
      (node (ref "R57") (pin "1") (pinfunction "1_1") (pintype "passive"))
      (node (ref "R59") (pin "1") (pinfunction "1_1") (pintype "passive"))
      (node (ref "R62") (pin "2") (pinfunction "2_2") (pintype "passive"))
    )
    (net (code "28") (name "Net-(Q15-G)") (class "Default")
      (node (ref "C106") (pin "2") (pinfunction "2_2") (pintype "passive"))
      (node (ref "Q15") (pin "1") (pinfunction "G_1") (pintype "passive"))
      (node (ref "Q16") (pin "1") (pinfunction "G_1") (pintype "passive"))
      (node (ref "R58") (pin "2") (pinfunction "2_2") (pintype "passive"))
      (node (ref "R63") (pin "2") (pinfunction "2_2") (pintype "passive"))
    )
    (net (code "29") (name "Net-(Q15-S)") (class "Default")
      (node (ref "C106") (pin "1") (pinfunction "1_1") (pintype "passive"))
      (node (ref "Q15") (pin "3") (pinfunction "S_3") (pintype "passive"))
      (node (ref "Q16") (pin "3") (pinfunction "S_3") (pintype "passive"))
      (node (ref "R58") (pin "1") (pinfunction "1_1") (pintype "passive"))
    )
    (net (code "30") (name "Net-(Q16-D)") (class "Default")
      (node (ref "D13") (pin "1") (pinfunction "1_1") (pintype "passive"))
      (node (ref "J9") (pin "2") (pinfunction "2_2") (pintype "passive"))
      (node (ref "Q16") (pin "2") (pinfunction "D_2") (pintype "passive"))
      (node (ref "R57") (pin "2") (pinfunction "2_2") (pintype "passive"))
    )
    (net (code "31") (name "Net-(U10-VCAP)") (class "Default")
      (node (ref "C43") (pin "1") (pinfunction "1_1") (pintype "passive"))
      (node (ref "U10") (pin "1") (pinfunction "VCAP_1") (pintype "power_in"))
    )
    (net (code "32") (name "Net-(U11-CELL_BATPRESZ)") (class "Default")
      (node (ref "R64") (pin "1") (pinfunction "1_1") (pintype "passive"))
      (node (ref "R7") (pin "1") (pinfunction "1_1") (pintype "passive"))
      (node (ref "U11") (pin "18") (pinfunction "CELL_BATPRESZ_18") (pintype "passive"))
    )
    (net (code "33") (name "Net-(U11-COMP1)") (class "Default")
      (node (ref "C65") (pin "1") (pinfunction "1_1") (pintype "passive"))
      (node (ref "R71") (pin "1") (pinfunction "1_1") (pintype "passive"))
      (node (ref "U11") (pin "16") (pinfunction "COMP1_16") (pintype "passive"))
    )
    (net (code "34") (name "Net-(U11-COMP2)") (class "Default")
      (node (ref "C62") (pin "2") (pinfunction "2_2") (pintype "passive"))
      (node (ref "R66") (pin "2") (pinfunction "2_2") (pintype "passive"))
      (node (ref "U11") (pin "17") (pinfunction "COMP2_17") (pintype "passive"))
    )
    (net (code "35") (name "Net-(U11-IADPT)") (class "Default")
      (node (ref "C63") (pin "1") (pinfunction "1_1") (pintype "passive"))
      (node (ref "R68") (pin "1") (pinfunction "1_1") (pintype "passive"))
      (node (ref "U11") (pin "8") (pinfunction "IADPT_8") (pintype "passive"))
    )
    (net (code "36") (name "Net-(U11-IBAT)") (class "Default")
      (node (ref "C66") (pin "1") (pinfunction "1_1") (pintype "passive"))
      (node (ref "U11") (pin "9") (pinfunction "IBAT_9") (pintype "passive"))
    )
    (net (code "37") (name "Net-(U11-PSYS)") (class "Default")
      (node (ref "R70") (pin "1") (pinfunction "1_1") (pintype "passive"))
      (node (ref "U11") (pin "10") (pinfunction "PSYS_10") (pintype "passive"))
    )
    (net (code "38") (name "Net-(U11-SRN)") (class "Default")
      (node (ref "R62") (pin "1") (pinfunction "1_1") (pintype "passive"))
      (node (ref "U11") (pin "19") (pinfunction "SRN_19") (pintype "passive"))
    )
    (net (code "39") (name "Net-(U11-SRP)") (class "Default")
      (node (ref "R61") (pin "1") (pinfunction "1_1") (pintype "passive"))
      (node (ref "U11") (pin "20") (pinfunction "SRP_20") (pintype "passive"))
    )
    (net (code "40") (name "Net-(U11-VBUS)") (class "Default")
      (node (ref "R60") (pin "1") (pinfunction "1_1") (pintype "passive"))
      (node (ref "U11") (pin "1") (pinfunction "VBUS_1") (pintype "passive"))
    )
    (net (code "41") (name "Net-(U16-VCAP)") (class "Default")
      (node (ref "C100") (pin "1") (pinfunction "1_1") (pintype "passive"))
      (node (ref "U16") (pin "1") (pinfunction "VCAP_1") (pintype "power_in"))
    )
    (net (code "42") (name "Net-(U17-A)") (class "Default")
      (node (ref "C103") (pin "2") (pinfunction "2_2") (pintype "passive"))
      (node (ref "D10") (pin "2") (pinfunction "A_2") (pintype "passive"))
      (node (ref "J8") (pin "1") (pinfunction "1_1") (pintype "passive"))
      (node (ref "Q14") (pin "1") (pinfunction "S_1") (pintype "passive"))
      (node (ref "Q14") (pin "2") (pinfunction "S_2") (pintype "passive"))
      (node (ref "Q14") (pin "3") (pinfunction "S_3") (pintype "passive"))
      (node (ref "U17") (pin "3") (pinfunction "EN_3") (pintype "input"))
      (node (ref "U17") (pin "6") (pinfunction "A_6") (pintype "passive"))
    )
    (net (code "43") (name "Net-(U17-VCAP)") (class "Default")
      (node (ref "C103") (pin "1") (pinfunction "1_1") (pintype "passive"))
      (node (ref "U17") (pin "1") (pinfunction "VCAP_1") (pintype "power_in"))
    )
    (net (code "44") (name "V_DDA") (class "Default")
      (node (ref "C61") (pin "2") (pinfunction "2_2") (pintype "passive"))
      (node (ref "R64") (pin "2") (pinfunction "2_2") (pintype "passive"))
      (node (ref "R65") (pin "1") (pinfunction "1_1") (pintype "passive"))
      (node (ref "R67") (pin "1") (pinfunction "1_1") (pintype "passive"))
      (node (ref "U11") (pin "7") (pinfunction "VDDA_7") (pintype "passive"))
    )
    (net (code "45") (name "V_IN_PROTECTED") (class "Default")
      (node (ref "C30") (pin "1") (pinfunction "1_1") (pintype "passive"))
      (node (ref "C31") (pin "1") (pinfunction "1_1") (pintype "passive"))
      (node (ref "C32") (pin "1") (pinfunction "1_1") (pintype "passive"))
      (node (ref "C33") (pin "1") (pinfunction "1_1") (pintype "passive"))
      (node (ref "C44") (pin "1") (pinfunction "1_1") (pintype "passive"))
      (node (ref "C45") (pin "1") (pinfunction "1_1") (pintype "passive"))
      (node (ref "C46") (pin "1") (pinfunction "1_1") (pintype "passive"))
      (node (ref "C47") (pin "1") (pinfunction "1_1") (pintype "passive"))
      (node (ref "Q7") (pin "5") (pinfunction "D_5") (pintype "passive"))
      (node (ref "Q7") (pin "6") (pinfunction "D_6") (pintype "passive"))
      (node (ref "Q7") (pin "7") (pinfunction "D_7") (pintype "passive"))
      (node (ref "Q7") (pin "8") (pinfunction "D_8") (pintype "passive"))
      (node (ref "Q7") (pin "9") (pinfunction "D_9") (pintype "passive"))
      (node (ref "R48") (pin "2") (pinfunction "2_2") (pintype "passive"))
      (node (ref "R53") (pin "2") (pinfunction "2_2") (pintype "passive"))
      (node (ref "R60") (pin "2") (pinfunction "2_2") (pintype "passive"))
      (node (ref "U10") (pin "4") (pinfunction "C_4") (pintype "passive"))
    )
    (net (code "46") (name "V_OUT") (class "Default")
      (node (ref "C100") (pin "2") (pinfunction "2_2") (pintype "passive"))
      (node (ref "C29") (pin "2") (pinfunction "2_2") (pintype "passive"))
      (node (ref "C34") (pin "1") (pinfunction "1_1") (pintype "passive"))
      (node (ref "C35") (pin "1") (pinfunction "1_1") (pintype "passive"))
      (node (ref "C36") (pin "1") (pinfunction "1_1") (pintype "passive"))
      (node (ref "C37") (pin "1") (pinfunction "1_1") (pintype "passive"))
      (node (ref "C48") (pin "1") (pinfunction "1_1") (pintype "passive"))
      (node (ref "C49") (pin "1") (pinfunction "1_1") (pintype "passive"))
      (node (ref "C50") (pin "1") (pinfunction "1_1") (pintype "passive"))
      (node (ref "C51") (pin "1") (pinfunction "1_1") (pintype "passive"))
      (node (ref "Q10") (pin "5-6-7-8") (pinfunction "D_5-6-7-8") (pintype "passive"))
      (node (ref "Q13") (pin "1") (pinfunction "1-2-3_1") (pintype "passive"))
      (node (ref "Q13") (pin "2") (pinfunction "S_2") (pintype "passive"))
      (node (ref "Q13") (pin "3") (pinfunction "S_3") (pintype "passive"))
      (node (ref "Q8") (pin "1") (pinfunction "1-2-3_1") (pintype "passive"))
      (node (ref "Q8") (pin "2") (pinfunction "S_2") (pintype "passive"))
      (node (ref "Q8") (pin "3") (pinfunction "S_3") (pintype "passive"))
      (node (ref "U11") (pin "22") (pinfunction "VSYS_22") (pintype "passive"))
      (node (ref "U16") (pin "3") (pinfunction "EN_3") (pintype "input"))
      (node (ref "U16") (pin "6") (pinfunction "A_6") (pintype "passive"))
    )
    (net (code "47") (name "V_SYS") (class "Default")
      (node (ref "R49") (pin "1") (pinfunction "1_1") (pintype "passive"))
    )
    (net (code "48") (name "unconnected-(U11-CHRG_OK-Pad4)") (class "Default")
      (node (ref "U11") (pin "4") (pinfunction "CHRG_OK_4") (pintype "passive"))
    )
    (net (code "49") (name "unconnected-(U11-CMPOUT-Pad15)") (class "Default")
      (node (ref "U11") (pin "15") (pinfunction "CMPOUT_15") (pintype "passive+no_connect"))
    )
    (net (code "50") (name "unconnected-(U11-~{PROCHOT}-Pad11)") (class "Default")
      (node (ref "U11") (pin "11") (pinfunction "~{PROCHOT}_11") (pintype "passive+no_connect"))
    )
  )
)
